# controlo_rev4.net
KiCad netlist of a schematic drawn in Altium Designer
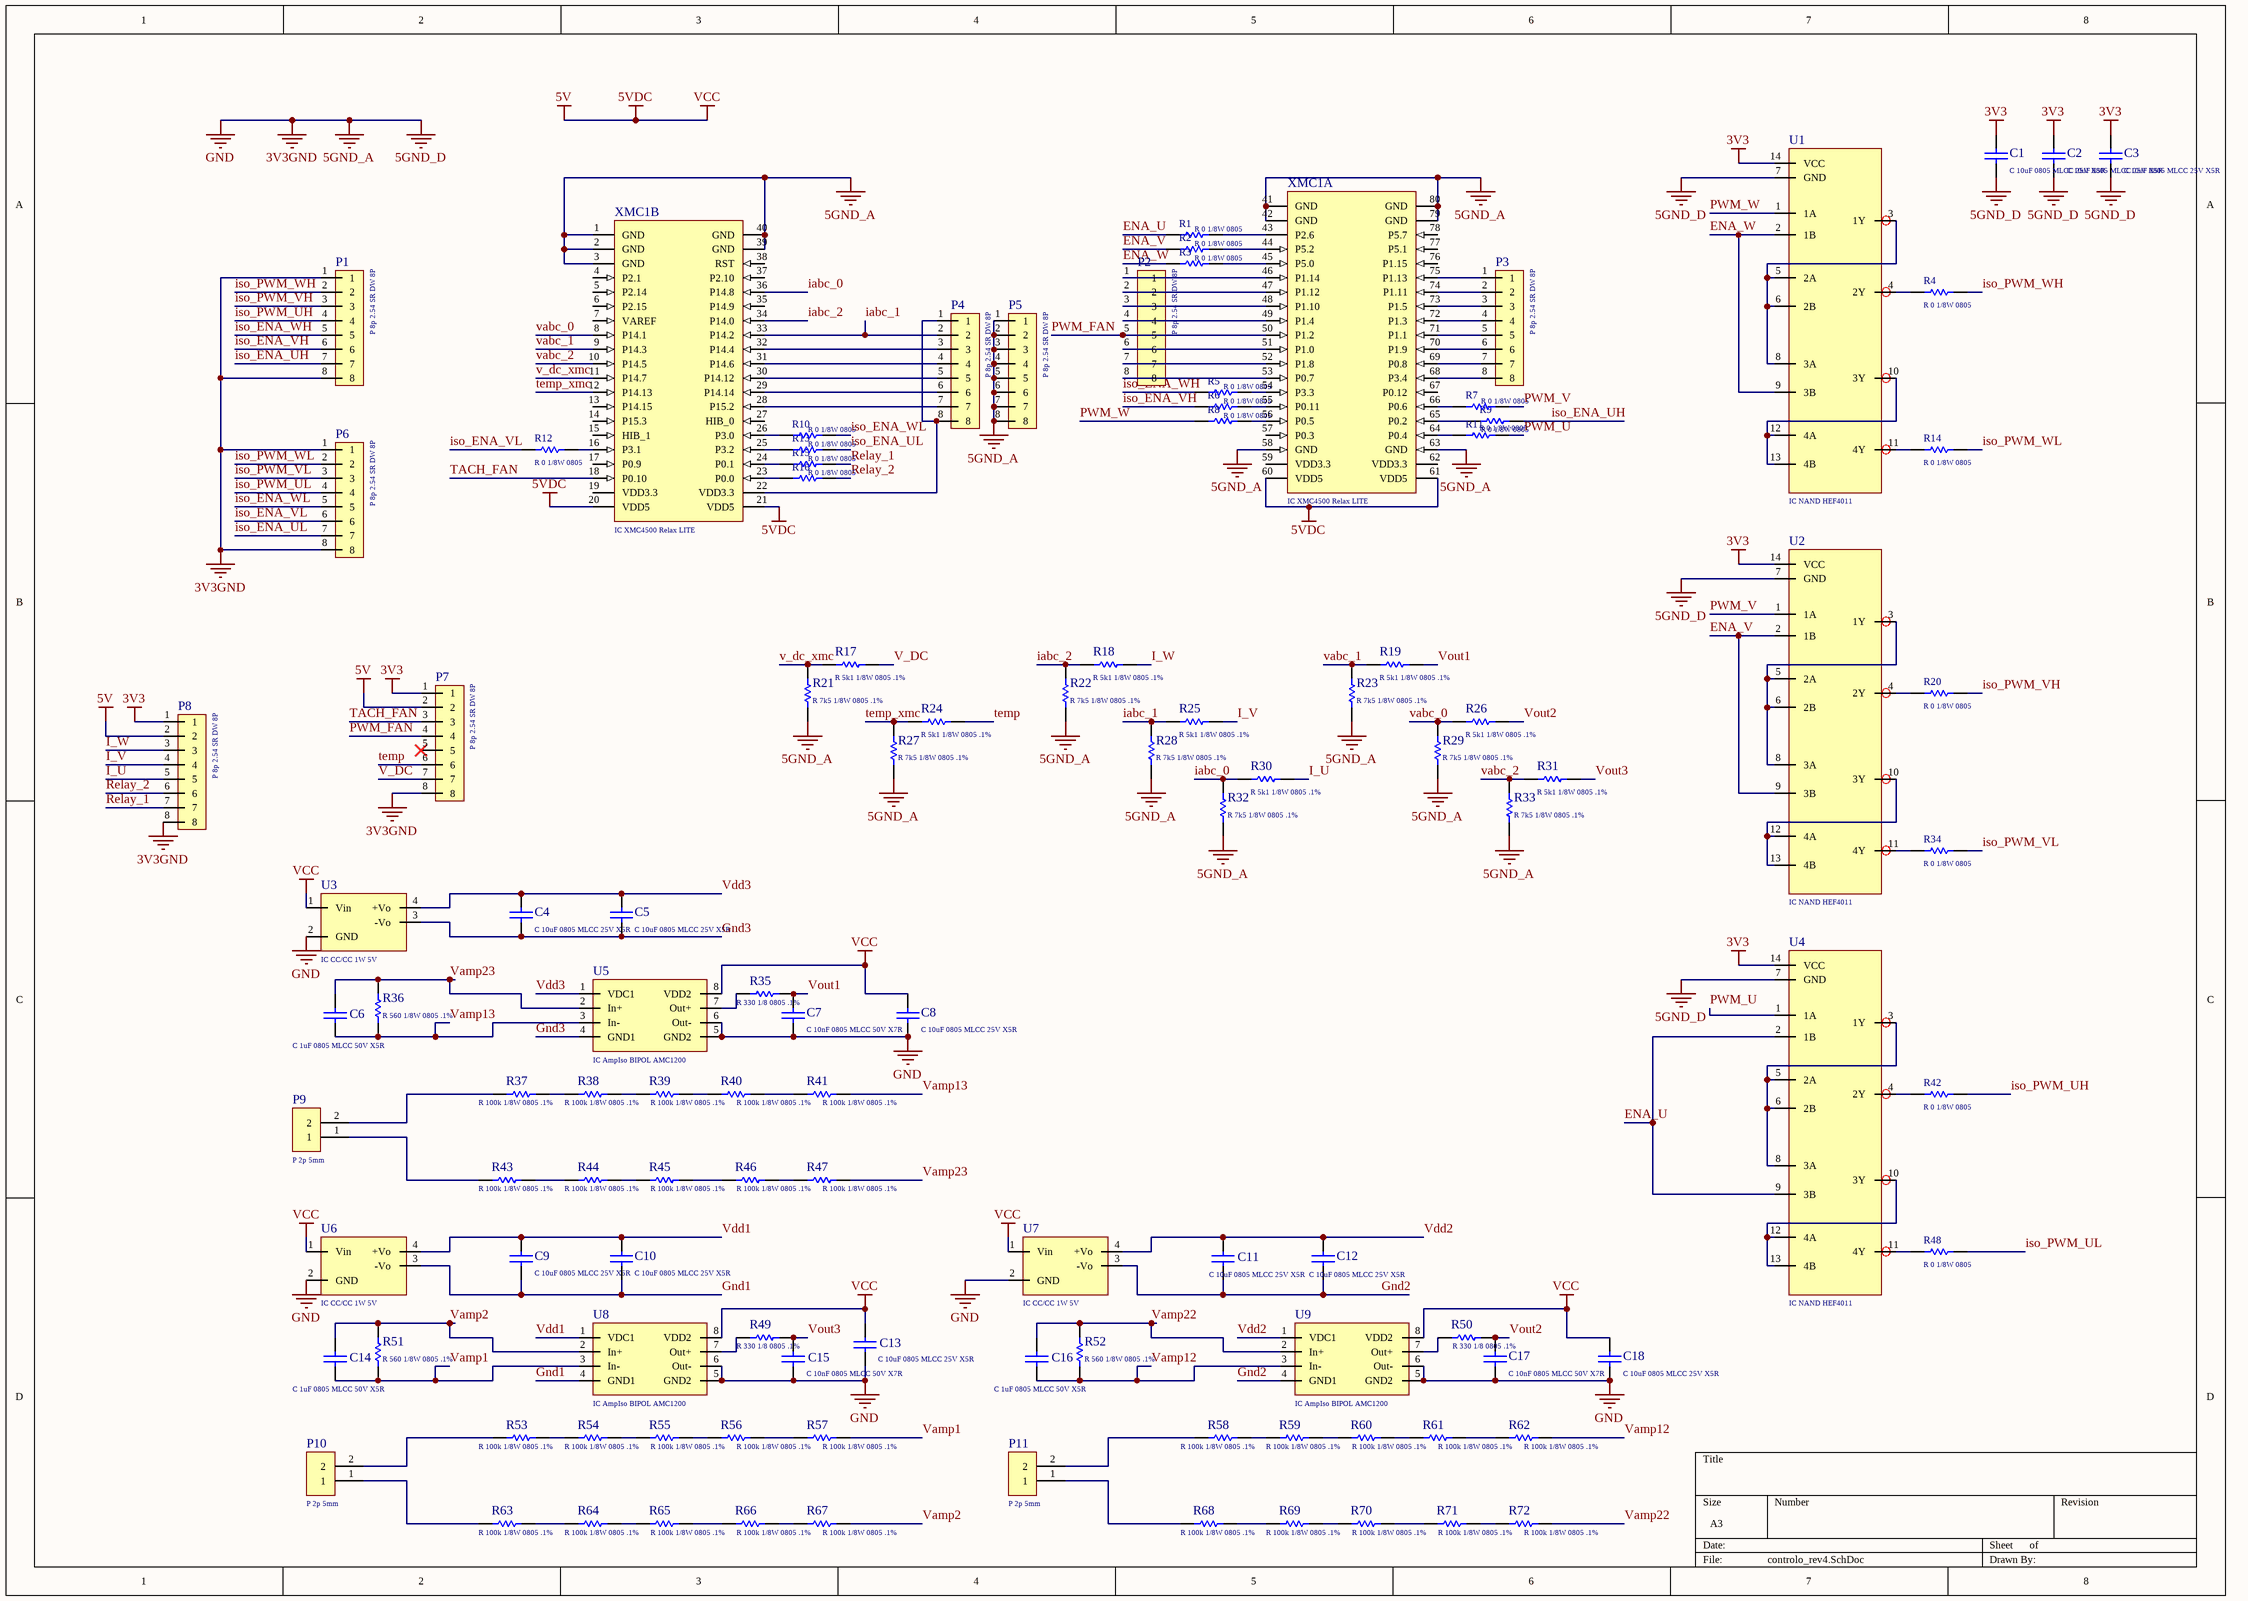
[diagram p0: controlo_rev4.SchDoc]

(export (version "E")
  (design (tool "Eeschema 10.0.6"))
  (components
    (comp (ref "C1")
      (value "C 10uF 0805 MLCC 25V X5R")
      (footprint "CAPC_0805")
      (description "Capacitores de cerâmica multicamada MLCC - SMD/SMT 10uF 25V X5R +/-10% 0805 Gen Purp")
      (fields (field (name "LCSC PART #") "C15850"))
      (libsource (lib "vi_measurement") (part "Capacitor SMD"))
    )
    (comp (ref "C2")
      (value "C 10uF 0805 MLCC 25V X5R")
      (footprint "CAPC_0805")
      (description "Capacitores de cerâmica multicamada MLCC - SMD/SMT 10uF 25V X5R +/-10% 0805 Gen Purp")
      (fields (field (name "LCSC PART #") "C15850"))
      (libsource (lib "vi_measurement") (part "Capacitor SMD"))
    )
    (comp (ref "C3")
      (value "C 10uF 0805 MLCC 25V X5R")
      (footprint "CAPC_0805")
      (description "Capacitores de cerâmica multicamada MLCC - SMD/SMT 10uF 25V X5R +/-10% 0805 Gen Purp")
      (fields (field (name "LCSC PART #") "C15850"))
      (libsource (lib "vi_measurement") (part "Capacitor SMD"))
    )
    (comp (ref "C4")
      (value "C 10uF 0805 MLCC 25V X5R")
      (footprint "CAPC_0805")
      (description "Capacitores de cerâmica multicamada MLCC - SMD/SMT 10uF 25V X5R +/-10% 0805 Gen Purp")
      (fields (field (name "LCSC PART #") "C15850"))
      (libsource (lib "vi_measurement") (part "Capacitor SMD"))
    )
    (comp (ref "C5")
      (value "C 10uF 0805 MLCC 25V X5R")
      (footprint "CAPC_0805")
      (description "Capacitores de cerâmica multicamada MLCC - SMD/SMT 10uF 25V X5R +/-10% 0805 Gen Purp")
      (fields (field (name "LCSC PART #") "C15850"))
      (libsource (lib "vi_measurement") (part "Capacitor SMD"))
    )
    (comp (ref "C6")
      (value "C 1uF 0805 MLCC 50V X5R")
      (footprint "CAPC_0805")
      (description "Capacitores de cerâmica multicamada MLCC - SMD/SMT 0805 50V 1uF 20% X5R")
      (fields (field (name "LCSC PART #") "C28323"))
      (libsource (lib "vi_measurement") (part "Capacitor SMD"))
    )
    (comp (ref "C7")
      (value "C 10nF 0805 MLCC 50V X7R")
      (footprint "CAPC_0805")
      (description "Capacitores de cerâmica multicamada MLCC - SMD/SMT 10nF 50V X7R 10%")
      (fields (field (name "LCSC PART #") "C1710"))
      (libsource (lib "vi_measurement") (part "Capacitor SMD"))
    )
    (comp (ref "C8")
      (value "C 10uF 0805 MLCC 25V X5R")
      (footprint "CAPC_0805")
      (description "Capacitores de cerâmica multicamada MLCC - SMD/SMT 10uF 25V X5R +/-10% 0805 Gen Purp")
      (fields (field (name "LCSC PART #") "C15850"))
      (libsource (lib "vi_measurement") (part "Capacitor SMD"))
    )
    (comp (ref "C9")
      (value "C 10uF 0805 MLCC 25V X5R")
      (footprint "CAPC_0805")
      (description "Capacitores de cerâmica multicamada MLCC - SMD/SMT 10uF 25V X5R +/-10% 0805 Gen Purp")
      (fields (field (name "LCSC PART #") "C15850"))
      (libsource (lib "vi_measurement") (part "Capacitor SMD"))
    )
    (comp (ref "C10")
      (value "C 10uF 0805 MLCC 25V X5R")
      (footprint "CAPC_0805")
      (description "Capacitores de cerâmica multicamada MLCC - SMD/SMT 10uF 25V X5R +/-10% 0805 Gen Purp")
      (fields (field (name "LCSC PART #") "C15850"))
      (libsource (lib "vi_measurement") (part "Capacitor SMD"))
    )
    (comp (ref "C11")
      (value "C 10uF 0805 MLCC 25V X5R")
      (footprint "CAPC_0805")
      (description "Capacitores de cerâmica multicamada MLCC - SMD/SMT 10uF 25V X5R +/-10% 0805 Gen Purp")
      (fields (field (name "LCSC PART #") "C15850"))
      (libsource (lib "vi_measurement") (part "Capacitor SMD"))
    )
    (comp (ref "C12")
      (value "C 10uF 0805 MLCC 25V X5R")
      (footprint "CAPC_0805")
      (description "Capacitores de cerâmica multicamada MLCC - SMD/SMT 10uF 25V X5R +/-10% 0805 Gen Purp")
      (fields (field (name "LCSC PART #") "C15850"))
      (libsource (lib "vi_measurement") (part "Capacitor SMD"))
    )
    (comp (ref "C13")
      (value "C 10uF 0805 MLCC 25V X5R")
      (footprint "CAPC_0805")
      (description "Capacitores de cerâmica multicamada MLCC - SMD/SMT 10uF 25V X5R +/-10% 0805 Gen Purp")
      (fields (field (name "LCSC PART #") "C15850"))
      (libsource (lib "vi_measurement") (part "Capacitor SMD"))
    )
    (comp (ref "C14")
      (value "C 1uF 0805 MLCC 50V X5R")
      (footprint "CAPC_0805")
      (description "Capacitores de cerâmica multicamada MLCC - SMD/SMT 0805 50V 1uF 20% X5R")
      (fields (field (name "LCSC PART #") "C28323"))
      (libsource (lib "vi_measurement") (part "Capacitor SMD"))
    )
    (comp (ref "C15")
      (value "C 10nF 0805 MLCC 50V X7R")
      (footprint "CAPC_0805")
      (description "Capacitores de cerâmica multicamada MLCC - SMD/SMT 10nF 50V X7R 10%")
      (fields (field (name "LCSC PART #") "C1710"))
      (libsource (lib "vi_measurement") (part "Capacitor SMD"))
    )
    (comp (ref "C16")
      (value "C 1uF 0805 MLCC 50V X5R")
      (footprint "CAPC_0805")
      (description "Capacitores de cerâmica multicamada MLCC - SMD/SMT 0805 50V 1uF 20% X5R")
      (fields (field (name "LCSC PART #") "C28323"))
      (libsource (lib "vi_measurement") (part "Capacitor SMD"))
    )
    (comp (ref "C17")
      (value "C 10nF 0805 MLCC 50V X7R")
      (footprint "CAPC_0805")
      (description "Capacitores de cerâmica multicamada MLCC - SMD/SMT 10nF 50V X7R 10%")
      (fields (field (name "LCSC PART #") "C1710"))
      (libsource (lib "vi_measurement") (part "Capacitor SMD"))
    )
    (comp (ref "C18")
      (value "C 10uF 0805 MLCC 25V X5R")
      (footprint "CAPC_0805")
      (description "Capacitores de cerâmica multicamada MLCC - SMD/SMT 10uF 25V X5R +/-10% 0805 Gen Purp")
      (fields (field (name "LCSC PART #") "C15850"))
      (libsource (lib "vi_measurement") (part "Capacitor SMD"))
    )
    (comp (ref "P1")
      (value "P 8p 2.54 SR DW 8P")
      (footprint "Header 8x1 8.5mm")
      (description "Distribuidores e Alojamento de Fios CGrid Hrd SRDW THo le 8ckt")
      (libsource (lib "vmorais_libraries") (part "jumper_8p"))
    )
    (comp (ref "P2")
      (value "P 8p 2.54 SR DW 8P")
      (footprint "Header 8x1 8.5mm")
      (description "Distribuidores e Alojamento de Fios CGrid Hrd SRDW THo le 8ckt")
      (libsource (lib "vmorais_libraries") (part "jumper_8p"))
    )
    (comp (ref "P3")
      (value "P 8p 2.54 SR DW 8P")
      (footprint "Header 8x1 8.5mm")
      (description "Distribuidores e Alojamento de Fios CGrid Hrd SRDW THo le 8ckt")
      (libsource (lib "vmorais_libraries") (part "jumper_8p"))
    )
    (comp (ref "P4")
      (value "P 8p 2.54 SR DW 8P")
      (footprint "Header 8x1 8.5mm")
      (description "Distribuidores e Alojamento de Fios CGrid Hrd SRDW THo le 8ckt")
      (libsource (lib "vmorais_libraries") (part "jumper_8p"))
    )
    (comp (ref "P5")
      (value "P 8p 2.54 SR DW 8P")
      (footprint "Header 8x1 8.5mm")
      (description "Distribuidores e Alojamento de Fios CGrid Hrd SRDW THo le 8ckt")
      (libsource (lib "vmorais_libraries") (part "jumper_8p"))
    )
    (comp (ref "P6")
      (value "P 8p 2.54 SR DW 8P")
      (footprint "Header 8x1 8.5mm")
      (description "Distribuidores e Alojamento de Fios CGrid Hrd SRDW THo le 8ckt")
      (libsource (lib "vmorais_libraries") (part "jumper_8p"))
    )
    (comp (ref "P7")
      (value "P 8p 2.54 SR DW 8P")
      (footprint "Header 8x1 8.5mm")
      (description "Distribuidores e Alojamento de Fios CGrid Hrd SRDW THo le 8ckt")
      (libsource (lib "vmorais_libraries") (part "jumper_8p"))
    )
    (comp (ref "P8")
      (value "P 8p 2.54 SR DW 8P")
      (footprint "Header 8x1 8.5mm")
      (description "Distribuidores e Alojamento de Fios CGrid Hrd SRDW THo le 8ckt")
      (libsource (lib "vmorais_libraries") (part "jumper_8p"))
    )
    (comp (ref "P9")
      (value "P 2p 5mm")
      (footprint "connector1x2_parafuso")
      (description "Bloques de terminales de PCB de perfil estándar RS de 5,0 mm")
      (libsource (lib "malvega_pcb") (part "gen_purpose_conn_1x2"))
    )
    (comp (ref "P10")
      (value "P 2p 5mm")
      (footprint "connector1x2_parafuso")
      (description "Bloques de terminales de PCB de perfil estándar RS de 5,0 mm")
      (libsource (lib "malvega_pcb") (part "gen_purpose_conn_1x2"))
    )
    (comp (ref "P11")
      (value "P 2p 5mm")
      (footprint "connector1x2_parafuso")
      (description "Bloques de terminales de PCB de perfil estándar RS de 5,0 mm")
      (libsource (lib "malvega_pcb") (part "gen_purpose_conn_1x2"))
    )
    (comp (ref "R1")
      (value "R 0 1/8W 0805")
      (footprint "RESC_0805")
      (description "Resistores de Filme Espesso - SMD 1/8Watt 0ohms Commercial Use")
      (fields (field (name "LCSC PART #") "C17477"))
      (libsource (lib "inversor_50a") (part "Resistor"))
    )
    (comp (ref "R2")
      (value "R 0 1/8W 0805")
      (footprint "RESC_0805")
      (description "Resistores de Filme Espesso - SMD 1/8Watt 0ohms Commercial Use")
      (fields (field (name "LCSC PART #") "C17477"))
      (libsource (lib "inversor_50a") (part "Resistor"))
    )
    (comp (ref "R3")
      (value "R 0 1/8W 0805")
      (footprint "RESC_0805")
      (description "Resistores de Filme Espesso - SMD 1/8Watt 0ohms Commercial Use")
      (fields (field (name "LCSC PART #") "C17477"))
      (libsource (lib "inversor_50a") (part "Resistor"))
    )
    (comp (ref "R4")
      (value "R 0 1/8W 0805")
      (footprint "RESC_0805")
      (description "Resistores de Filme Espesso - SMD 1/8Watt 0ohms Commercial Use")
      (fields (field (name "LCSC PART #") "C17477"))
      (libsource (lib "inversor_50a") (part "Resistor"))
    )
    (comp (ref "R5")
      (value "R 0 1/8W 0805")
      (footprint "RESC_0805")
      (description "Resistores de Filme Espesso - SMD 1/8Watt 0ohms Commercial Use")
      (fields (field (name "LCSC PART #") "C17477"))
      (libsource (lib "inversor_50a") (part "Resistor"))
    )
    (comp (ref "R6")
      (value "R 0 1/8W 0805")
      (footprint "RESC_0805")
      (description "Resistores de Filme Espesso - SMD 1/8Watt 0ohms Commercial Use")
      (fields (field (name "LCSC PART #") "C17477"))
      (libsource (lib "inversor_50a") (part "Resistor"))
    )
    (comp (ref "R7")
      (value "R 0 1/8W 0805")
      (footprint "RESC_0805")
      (description "Resistores de Filme Espesso - SMD 1/8Watt 0ohms Commercial Use")
      (fields (field (name "LCSC PART #") "C17477"))
      (libsource (lib "inversor_50a") (part "Resistor"))
    )
    (comp (ref "R8")
      (value "R 0 1/8W 0805")
      (footprint "RESC_0805")
      (description "Resistores de Filme Espesso - SMD 1/8Watt 0ohms Commercial Use")
      (fields (field (name "LCSC PART #") "C17477"))
      (libsource (lib "inversor_50a") (part "Resistor"))
    )
    (comp (ref "R9")
      (value "R 0 1/8W 0805")
      (footprint "RESC_0805")
      (description "Resistores de Filme Espesso - SMD 1/8Watt 0ohms Commercial Use")
      (fields (field (name "LCSC PART #") "C17477"))
      (libsource (lib "inversor_50a") (part "Resistor"))
    )
    (comp (ref "R10")
      (value "R 0 1/8W 0805")
      (footprint "RESC_0805")
      (description "Resistores de Filme Espesso - SMD 1/8Watt 0ohms Commercial Use")
      (fields (field (name "LCSC PART #") "C17477"))
      (libsource (lib "inversor_50a") (part "Resistor"))
    )
    (comp (ref "R11")
      (value "R 0 1/8W 0805")
      (footprint "RESC_0805")
      (description "Resistores de Filme Espesso - SMD 1/8Watt 0ohms Commercial Use")
      (fields (field (name "LCSC PART #") "C17477"))
      (libsource (lib "inversor_50a") (part "Resistor"))
    )
    (comp (ref "R12")
      (value "R 0 1/8W 0805")
      (footprint "RESC_0805")
      (description "Resistores de Filme Espesso - SMD 1/8Watt 0ohms Commercial Use")
      (fields (field (name "LCSC PART #") "C17477"))
      (libsource (lib "inversor_50a") (part "Resistor"))
    )
    (comp (ref "R13")
      (value "R 0 1/8W 0805")
      (footprint "RESC_0805")
      (description "Resistores de Filme Espesso - SMD 1/8Watt 0ohms Commercial Use")
      (fields (field (name "LCSC PART #") "C17477"))
      (libsource (lib "inversor_50a") (part "Resistor"))
    )
    (comp (ref "R14")
      (value "R 0 1/8W 0805")
      (footprint "RESC_0805")
      (description "Resistores de Filme Espesso - SMD 1/8Watt 0ohms Commercial Use")
      (fields (field (name "LCSC PART #") "C17477"))
      (libsource (lib "inversor_50a") (part "Resistor"))
    )
    (comp (ref "R15")
      (value "R 0 1/8W 0805")
      (footprint "RESC_0805")
      (description "Resistores de Filme Espesso - SMD 1/8Watt 0ohms Commercial Use")
      (fields (field (name "LCSC PART #") "C17477"))
      (libsource (lib "inversor_50a") (part "Resistor"))
    )
    (comp (ref "R16")
      (value "R 0 1/8W 0805")
      (footprint "RESC_0805")
      (description "Resistores de Filme Espesso - SMD 1/8Watt 0ohms Commercial Use")
      (fields (field (name "LCSC PART #") "C17477"))
      (libsource (lib "inversor_50a") (part "Resistor"))
    )
    (comp (ref "R17")
      (value "R 5k1 1/8W 0805 .1%")
      (footprint "RESC_0805")
      (description "Resistores de Filme Fino - SMD 0805 5.1Kohm 1/8W .1% 25ppm")
      (fields (field (name "LCSC PART #") "C27834"))
      (libsource (lib "inversor_50a") (part "Resistor"))
    )
    (comp (ref "R18")
      (value "R 5k1 1/8W 0805 .1%")
      (footprint "RESC_0805")
      (description "Resistores de Filme Fino - SMD 0805 5.1Kohm 1/8W .1% 25ppm")
      (fields (field (name "LCSC PART #") "C27834"))
      (libsource (lib "inversor_50a") (part "Resistor"))
    )
    (comp (ref "R19")
      (value "R 5k1 1/8W 0805 .1%")
      (footprint "RESC_0805")
      (description "Resistores de Filme Fino - SMD 0805 5.1Kohm 1/8W .1% 25ppm")
      (fields (field (name "LCSC PART #") "C27834"))
      (libsource (lib "inversor_50a") (part "Resistor"))
    )
    (comp (ref "R20")
      (value "R 0 1/8W 0805")
      (footprint "RESC_0805")
      (description "Resistores de Filme Espesso - SMD 1/8Watt 0ohms Commercial Use")
      (fields (field (name "LCSC PART #") "C17477"))
      (libsource (lib "inversor_50a") (part "Resistor"))
    )
    (comp (ref "R21")
      (value "R 7k5 1/8W 0805 .1%")
      (footprint "RESC_0805")
      (description "Resistores de Filme Fino - SMD 7.5K OHM .1% 25ppm")
      (fields (field (name "LCSC PART #") "C17807"))
      (libsource (lib "inversor_50a") (part "Resistor"))
    )
    (comp (ref "R22")
      (value "R 7k5 1/8W 0805 .1%")
      (footprint "RESC_0805")
      (description "Resistores de Filme Fino - SMD 7.5K OHM .1% 25ppm")
      (fields (field (name "LCSC PART #") "C17807"))
      (libsource (lib "inversor_50a") (part "Resistor"))
    )
    (comp (ref "R23")
      (value "R 7k5 1/8W 0805 .1%")
      (footprint "RESC_0805")
      (description "Resistores de Filme Fino - SMD 7.5K OHM .1% 25ppm")
      (fields (field (name "LCSC PART #") "C17807"))
      (libsource (lib "inversor_50a") (part "Resistor"))
    )
    (comp (ref "R24")
      (value "R 5k1 1/8W 0805 .1%")
      (footprint "RESC_0805")
      (description "Resistores de Filme Fino - SMD 0805 5.1Kohm 1/8W .1% 25ppm")
      (fields (field (name "LCSC PART #") "C27834"))
      (libsource (lib "inversor_50a") (part "Resistor"))
    )
    (comp (ref "R25")
      (value "R 5k1 1/8W 0805 .1%")
      (footprint "RESC_0805")
      (description "Resistores de Filme Fino - SMD 0805 5.1Kohm 1/8W .1% 25ppm")
      (fields (field (name "LCSC PART #") "C27834"))
      (libsource (lib "inversor_50a") (part "Resistor"))
    )
    (comp (ref "R26")
      (value "R 5k1 1/8W 0805 .1%")
      (footprint "RESC_0805")
      (description "Resistores de Filme Fino - SMD 0805 5.1Kohm 1/8W .1% 25ppm")
      (fields (field (name "LCSC PART #") "C27834"))
      (libsource (lib "inversor_50a") (part "Resistor"))
    )
    (comp (ref "R27")
      (value "R 7k5 1/8W 0805 .1%")
      (footprint "RESC_0805")
      (description "Resistores de Filme Fino - SMD 7.5K OHM .1% 25ppm")
      (fields (field (name "LCSC PART #") "C17807"))
      (libsource (lib "inversor_50a") (part "Resistor"))
    )
    (comp (ref "R28")
      (value "R 7k5 1/8W 0805 .1%")
      (footprint "RESC_0805")
      (description "Resistores de Filme Fino - SMD 7.5K OHM .1% 25ppm")
      (fields (field (name "LCSC PART #") "C17807"))
      (libsource (lib "inversor_50a") (part "Resistor"))
    )
    (comp (ref "R29")
      (value "R 7k5 1/8W 0805 .1%")
      (footprint "RESC_0805")
      (description "Resistores de Filme Fino - SMD 7.5K OHM .1% 25ppm")
      (fields (field (name "LCSC PART #") "C17807"))
      (libsource (lib "inversor_50a") (part "Resistor"))
    )
    (comp (ref "R30")
      (value "R 5k1 1/8W 0805 .1%")
      (footprint "RESC_0805")
      (description "Resistores de Filme Fino - SMD 0805 5.1Kohm 1/8W .1% 25ppm")
      (fields (field (name "LCSC PART #") "C27834"))
      (libsource (lib "inversor_50a") (part "Resistor"))
    )
    (comp (ref "R31")
      (value "R 5k1 1/8W 0805 .1%")
      (footprint "RESC_0805")
      (description "Resistores de Filme Fino - SMD 0805 5.1Kohm 1/8W .1% 25ppm")
      (fields (field (name "LCSC PART #") "C27834"))
      (libsource (lib "inversor_50a") (part "Resistor"))
    )
    (comp (ref "R32")
      (value "R 7k5 1/8W 0805 .1%")
      (footprint "RESC_0805")
      (description "Resistores de Filme Fino - SMD 7.5K OHM .1% 25ppm")
      (fields (field (name "LCSC PART #") "C17807"))
      (libsource (lib "inversor_50a") (part "Resistor"))
    )
    (comp (ref "R33")
      (value "R 7k5 1/8W 0805 .1%")
      (footprint "RESC_0805")
      (description "Resistores de Filme Fino - SMD 7.5K OHM .1% 25ppm")
      (fields (field (name "LCSC PART #") "C17807"))
      (libsource (lib "inversor_50a") (part "Resistor"))
    )
    (comp (ref "R34")
      (value "R 0 1/8W 0805")
      (footprint "RESC_0805")
      (description "Resistores de Filme Espesso - SMD 1/8Watt 0ohms Commercial Use")
      (fields (field (name "LCSC PART #") "C17477"))
      (libsource (lib "inversor_50a") (part "Resistor"))
    )
    (comp (ref "R35")
      (value "R 330 1/8 0805 .1%")
      (footprint "RESC_0805")
      (description "Resistores de Filme Fino - SMD CPF 0805 330R 0.1% 25PPM 1K RL")
      (fields (field (name "LCSC PART #") "C17630"))
      (libsource (lib "inversor_50a") (part "Resistor"))
    )
    (comp (ref "R36")
      (value "R 560 1/8W 0805 .1%")
      (footprint "RESC_0805")
      (description "Resistores de Filme Fino - SMD 1/8W 3.6K ohm .1% 25ppm")
      (fields (field (name "LCSC PART #") "C28636"))
      (libsource (lib "inversor_50a") (part "Resistor"))
    )
    (comp (ref "R37")
      (value "R 100k 1/8W 0805 .1%")
      (footprint "RESC_0805")
      (description "Resistores de Filme Fino - SMD 100 Kohm .1% 0805 25PPM")
      (fields (field (name "LCSC PART #") "C17407"))
      (libsource (lib "inversor_50a") (part "Resistor"))
    )
    (comp (ref "R38")
      (value "R 100k 1/8W 0805 .1%")
      (footprint "RESC_0805")
      (description "Resistores de Filme Fino - SMD 100 Kohm .1% 0805 25PPM")
      (fields (field (name "LCSC PART #") "C17407"))
      (libsource (lib "inversor_50a") (part "Resistor"))
    )
    (comp (ref "R39")
      (value "R 100k 1/8W 0805 .1%")
      (footprint "RESC_0805")
      (description "Resistores de Filme Fino - SMD 100 Kohm .1% 0805 25PPM")
      (fields (field (name "LCSC PART #") "C17407"))
      (libsource (lib "inversor_50a") (part "Resistor"))
    )
    (comp (ref "R40")
      (value "R 100k 1/8W 0805 .1%")
      (footprint "RESC_0805")
      (description "Resistores de Filme Fino - SMD 100 Kohm .1% 0805 25PPM")
      (fields (field (name "LCSC PART #") "C17407"))
      (libsource (lib "inversor_50a") (part "Resistor"))
    )
    (comp (ref "R41")
      (value "R 100k 1/8W 0805 .1%")
      (footprint "RESC_0805")
      (description "Resistores de Filme Fino - SMD 100 Kohm .1% 0805 25PPM")
      (fields (field (name "LCSC PART #") "C17407"))
      (libsource (lib "inversor_50a") (part "Resistor"))
    )
    (comp (ref "R42")
      (value "R 0 1/8W 0805")
      (footprint "RESC_0805")
      (description "Resistores de Filme Espesso - SMD 1/8Watt 0ohms Commercial Use")
      (fields (field (name "LCSC PART #") "C17477"))
      (libsource (lib "inversor_50a") (part "Resistor"))
    )
    (comp (ref "R43")
      (value "R 100k 1/8W 0805 .1%")
      (footprint "RESC_0805")
      (description "Resistores de Filme Fino - SMD 100 Kohm .1% 0805 25PPM")
      (fields (field (name "LCSC PART #") "C17407"))
      (libsource (lib "inversor_50a") (part "Resistor"))
    )
    (comp (ref "R44")
      (value "R 100k 1/8W 0805 .1%")
      (footprint "RESC_0805")
      (description "Resistores de Filme Fino - SMD 100 Kohm .1% 0805 25PPM")
      (fields (field (name "LCSC PART #") "C17407"))
      (libsource (lib "inversor_50a") (part "Resistor"))
    )
    (comp (ref "R45")
      (value "R 100k 1/8W 0805 .1%")
      (footprint "RESC_0805")
      (description "Resistores de Filme Fino - SMD 100 Kohm .1% 0805 25PPM")
      (fields (field (name "LCSC PART #") "C17407"))
      (libsource (lib "inversor_50a") (part "Resistor"))
    )
    (comp (ref "R46")
      (value "R 100k 1/8W 0805 .1%")
      (footprint "RESC_0805")
      (description "Resistores de Filme Fino - SMD 100 Kohm .1% 0805 25PPM")
      (fields (field (name "LCSC PART #") "C17407"))
      (libsource (lib "inversor_50a") (part "Resistor"))
    )
    (comp (ref "R47")
      (value "R 100k 1/8W 0805 .1%")
      (footprint "RESC_0805")
      (description "Resistores de Filme Fino - SMD 100 Kohm .1% 0805 25PPM")
      (fields (field (name "LCSC PART #") "C17407"))
      (libsource (lib "inversor_50a") (part "Resistor"))
    )
    (comp (ref "R48")
      (value "R 0 1/8W 0805")
      (footprint "RESC_0805")
      (description "Resistores de Filme Espesso - SMD 1/8Watt 0ohms Commercial Use")
      (fields (field (name "LCSC PART #") "C17477"))
      (libsource (lib "inversor_50a") (part "Resistor"))
    )
    (comp (ref "R49")
      (value "R 330 1/8 0805 .1%")
      (footprint "RESC_0805")
      (description "Resistores de Filme Fino - SMD CPF 0805 330R 0.1% 25PPM 1K RL")
      (fields (field (name "LCSC PART #") "C17630"))
      (libsource (lib "inversor_50a") (part "Resistor"))
    )
    (comp (ref "R50")
      (value "R 330 1/8 0805 .1%")
      (footprint "RESC_0805")
      (description "Resistores de Filme Fino - SMD CPF 0805 330R 0.1% 25PPM 1K RL")
      (fields (field (name "LCSC PART #") "C17630"))
      (libsource (lib "inversor_50a") (part "Resistor"))
    )
    (comp (ref "R51")
      (value "R 560 1/8W 0805 .1%")
      (footprint "RESC_0805")
      (description "Resistores de Filme Fino - SMD 1/8W 3.6K ohm .1% 25ppm")
      (fields (field (name "LCSC PART #") "C28636"))
      (libsource (lib "inversor_50a") (part "Resistor"))
    )
    (comp (ref "R52")
      (value "R 560 1/8W 0805 .1%")
      (footprint "RESC_0805")
      (description "Resistores de Filme Fino - SMD 1/8W 3.6K ohm .1% 25ppm")
      (fields (field (name "LCSC PART #") "C28636"))
      (libsource (lib "inversor_50a") (part "Resistor"))
    )
    (comp (ref "R53")
      (value "R 100k 1/8W 0805 .1%")
      (footprint "RESC_0805")
      (description "Resistores de Filme Fino - SMD 100 Kohm .1% 0805 25PPM")
      (fields (field (name "LCSC PART #") "C17407"))
      (libsource (lib "inversor_50a") (part "Resistor"))
    )
    (comp (ref "R54")
      (value "R 100k 1/8W 0805 .1%")
      (footprint "RESC_0805")
      (description "Resistores de Filme Fino - SMD 100 Kohm .1% 0805 25PPM")
      (fields (field (name "LCSC PART #") "C17407"))
      (libsource (lib "inversor_50a") (part "Resistor"))
    )
    (comp (ref "R55")
      (value "R 100k 1/8W 0805 .1%")
      (footprint "RESC_0805")
      (description "Resistores de Filme Fino - SMD 100 Kohm .1% 0805 25PPM")
      (fields (field (name "LCSC PART #") "C17407"))
      (libsource (lib "inversor_50a") (part "Resistor"))
    )
    (comp (ref "R56")
      (value "R 100k 1/8W 0805 .1%")
      (footprint "RESC_0805")
      (description "Resistores de Filme Fino - SMD 100 Kohm .1% 0805 25PPM")
      (fields (field (name "LCSC PART #") "C17407"))
      (libsource (lib "inversor_50a") (part "Resistor"))
    )
    (comp (ref "R57")
      (value "R 100k 1/8W 0805 .1%")
      (footprint "RESC_0805")
      (description "Resistores de Filme Fino - SMD 100 Kohm .1% 0805 25PPM")
      (fields (field (name "LCSC PART #") "C17407"))
      (libsource (lib "inversor_50a") (part "Resistor"))
    )
    (comp (ref "R58")
      (value "R 100k 1/8W 0805 .1%")
      (footprint "RESC_0805")
      (description "Resistores de Filme Fino - SMD 100 Kohm .1% 0805 25PPM")
      (fields (field (name "LCSC PART #") "C17407"))
      (libsource (lib "inversor_50a") (part "Resistor"))
    )
    (comp (ref "R59")
      (value "R 100k 1/8W 0805 .1%")
      (footprint "RESC_0805")
      (description "Resistores de Filme Fino - SMD 100 Kohm .1% 0805 25PPM")
      (fields (field (name "LCSC PART #") "C17407"))
      (libsource (lib "inversor_50a") (part "Resistor"))
    )
    (comp (ref "R60")
      (value "R 100k 1/8W 0805 .1%")
      (footprint "RESC_0805")
      (description "Resistores de Filme Fino - SMD 100 Kohm .1% 0805 25PPM")
      (fields (field (name "LCSC PART #") "C17407"))
      (libsource (lib "inversor_50a") (part "Resistor"))
    )
    (comp (ref "R61")
      (value "R 100k 1/8W 0805 .1%")
      (footprint "RESC_0805")
      (description "Resistores de Filme Fino - SMD 100 Kohm .1% 0805 25PPM")
      (fields (field (name "LCSC PART #") "C17407"))
      (libsource (lib "inversor_50a") (part "Resistor"))
    )
    (comp (ref "R62")
      (value "R 100k 1/8W 0805 .1%")
      (footprint "RESC_0805")
      (description "Resistores de Filme Fino - SMD 100 Kohm .1% 0805 25PPM")
      (fields (field (name "LCSC PART #") "C17407"))
      (libsource (lib "inversor_50a") (part "Resistor"))
    )
    (comp (ref "R63")
      (value "R 100k 1/8W 0805 .1%")
      (footprint "RESC_0805")
      (description "Resistores de Filme Fino - SMD 100 Kohm .1% 0805 25PPM")
      (fields (field (name "LCSC PART #") "C17407"))
      (libsource (lib "inversor_50a") (part "Resistor"))
    )
    (comp (ref "R64")
      (value "R 100k 1/8W 0805 .1%")
      (footprint "RESC_0805")
      (description "Resistores de Filme Fino - SMD 100 Kohm .1% 0805 25PPM")
      (fields (field (name "LCSC PART #") "C17407"))
      (libsource (lib "inversor_50a") (part "Resistor"))
    )
    (comp (ref "R65")
      (value "R 100k 1/8W 0805 .1%")
      (footprint "RESC_0805")
      (description "Resistores de Filme Fino - SMD 100 Kohm .1% 0805 25PPM")
      (fields (field (name "LCSC PART #") "C17407"))
      (libsource (lib "inversor_50a") (part "Resistor"))
    )
    (comp (ref "R66")
      (value "R 100k 1/8W 0805 .1%")
      (footprint "RESC_0805")
      (description "Resistores de Filme Fino - SMD 100 Kohm .1% 0805 25PPM")
      (fields (field (name "LCSC PART #") "C17407"))
      (libsource (lib "inversor_50a") (part "Resistor"))
    )
    (comp (ref "R67")
      (value "R 100k 1/8W 0805 .1%")
      (footprint "RESC_0805")
      (description "Resistores de Filme Fino - SMD 100 Kohm .1% 0805 25PPM")
      (fields (field (name "LCSC PART #") "C17407"))
      (libsource (lib "inversor_50a") (part "Resistor"))
    )
    (comp (ref "R68")
      (value "R 100k 1/8W 0805 .1%")
      (footprint "RESC_0805")
      (description "Resistores de Filme Fino - SMD 100 Kohm .1% 0805 25PPM")
      (fields (field (name "LCSC PART #") "C17407"))
      (libsource (lib "inversor_50a") (part "Resistor"))
    )
    (comp (ref "R69")
      (value "R 100k 1/8W 0805 .1%")
      (footprint "RESC_0805")
      (description "Resistores de Filme Fino - SMD 100 Kohm .1% 0805 25PPM")
      (fields (field (name "LCSC PART #") "C17407"))
      (libsource (lib "inversor_50a") (part "Resistor"))
    )
    (comp (ref "R70")
      (value "R 100k 1/8W 0805 .1%")
      (footprint "RESC_0805")
      (description "Resistores de Filme Fino - SMD 100 Kohm .1% 0805 25PPM")
      (fields (field (name "LCSC PART #") "C17407"))
      (libsource (lib "inversor_50a") (part "Resistor"))
    )
    (comp (ref "R71")
      (value "R 100k 1/8W 0805 .1%")
      (footprint "RESC_0805")
      (description "Resistores de Filme Fino - SMD 100 Kohm .1% 0805 25PPM")
      (fields (field (name "LCSC PART #") "C17407"))
      (libsource (lib "inversor_50a") (part "Resistor"))
    )
    (comp (ref "R72")
      (value "R 100k 1/8W 0805 .1%")
      (footprint "RESC_0805")
      (description "Resistores de Filme Fino - SMD 100 Kohm .1% 0805 25PPM")
      (fields (field (name "LCSC PART #") "C17407"))
      (libsource (lib "inversor_50a") (part "Resistor"))
    )
    (comp (ref "U1")
      (value "IC NAND HEF4011")
      (footprint "SOIC-14N")
      (description "Portas lógicas QUADRUPLE 2-INPUT NAND GATE")
      (fields (field (name "LCSC PART #") "C6725"))
      (libsource (lib "vmorais_libraries") (part "HEF4011"))
    )
    (comp (ref "U2")
      (value "IC NAND HEF4011")
      (footprint "SOIC-14N")
      (description "Portas lógicas QUADRUPLE 2-INPUT NAND GATE")
      (fields (field (name "LCSC PART #") "C6725"))
      (libsource (lib "vmorais_libraries") (part "HEF4011"))
    )
    (comp (ref "U3")
      (value "IC CC/CC 1W 5V")
      (footprint "DC/DC_ISO")
      (description "Conversores CC/CC com isolação 1W 5Vin 5Vout 200mA SIP7")
      (libsource (lib "vi_measurement") (part "DC/DC_ISO"))
    )
    (comp (ref "U4")
      (value "IC NAND HEF4011")
      (footprint "SOIC-14N")
      (description "Portas lógicas QUADRUPLE 2-INPUT NAND GATE")
      (fields (field (name "LCSC PART #") "C6725"))
      (libsource (lib "vmorais_libraries") (part "HEF4011"))
    )
    (comp (ref "U5")
      (value "IC AmpIso BIPOL AMC1200")
      (footprint "SOIC8")
      (description "Amplificadores de isolamento 4kV peak Iso Amp")
      (fields (field (name "LCSC PART #") "C79905"))
      (libsource (lib "vi_measurement") (part "AMC1200"))
    )
    (comp (ref "U6")
      (value "IC CC/CC 1W 5V")
      (footprint "DC/DC_ISO")
      (description "Conversores CC/CC com isolação 1W 5Vin 5Vout 200mA SIP7")
      (libsource (lib "vi_measurement") (part "DC/DC_ISO"))
    )
    (comp (ref "U7")
      (value "IC CC/CC 1W 5V")
      (footprint "DC/DC_ISO")
      (description "Conversores CC/CC com isolação 1W 5Vin 5Vout 200mA SIP7")
      (libsource (lib "vi_measurement") (part "DC/DC_ISO"))
    )
    (comp (ref "U8")
      (value "IC AmpIso BIPOL AMC1200")
      (footprint "SOIC8")
      (description "Amplificadores de isolamento 4kV peak Iso Amp")
      (fields (field (name "LCSC PART #") "C79905"))
      (libsource (lib "vi_measurement") (part "AMC1200"))
    )
    (comp (ref "U9")
      (value "IC AmpIso BIPOL AMC1200")
      (footprint "SOIC8")
      (description "Amplificadores de isolamento 4kV peak Iso Amp")
      (fields (field (name "LCSC PART #") "C79905"))
      (libsource (lib "vi_measurement") (part "AMC1200"))
    )
    (comp (ref "XMC1")
      (value "IC XMC4500 Relax LITE")
      (footprint "XMC4500")
      (libsource (lib "vmorais_libraries") (part "XMC4500"))
    )
  )
  (nets
    (net (code "1") (name "/ENA_U") (class "Default")
      (node (ref "R1") (pin "1") (pinfunction "1_1") (pintype "passive"))
      (node (ref "U4") (pin "2") (pinfunction "1B_2") (pintype "passive"))
      (node (ref "U4") (pin "9") (pinfunction "3B_9") (pintype "passive"))
    )
    (net (code "2") (name "/ENA_V") (class "Default")
      (node (ref "R2") (pin "1") (pinfunction "1_1") (pintype "passive"))
      (node (ref "U2") (pin "2") (pinfunction "1B_2") (pintype "passive"))
      (node (ref "U2") (pin "9") (pinfunction "3B_9") (pintype "passive"))
    )
    (net (code "3") (name "/ENA_W") (class "Default")
      (node (ref "R3") (pin "1") (pinfunction "1_1") (pintype "passive"))
      (node (ref "U1") (pin "2") (pinfunction "1B_2") (pintype "passive"))
      (node (ref "U1") (pin "9") (pinfunction "3B_9") (pintype "passive"))
    )
    (net (code "4") (name "/Gnd1") (class "Default")
      (node (ref "C10") (pin "1") (pinfunction "1_1") (pintype "passive"))
      (node (ref "C9") (pin "1") (pinfunction "1_1") (pintype "passive"))
      (node (ref "U6") (pin "3") (pinfunction "-Vo_3") (pintype "passive"))
      (node (ref "U8") (pin "4") (pinfunction "GND1_4") (pintype "passive"))
    )
    (net (code "5") (name "/Gnd2") (class "Default")
      (node (ref "C11") (pin "1") (pinfunction "1_1") (pintype "passive"))
      (node (ref "C12") (pin "1") (pinfunction "1_1") (pintype "passive"))
      (node (ref "U7") (pin "3") (pinfunction "-Vo_3") (pintype "passive"))
      (node (ref "U9") (pin "4") (pinfunction "GND1_4") (pintype "passive"))
    )
    (net (code "6") (name "/Gnd3") (class "Default")
      (node (ref "C4") (pin "1") (pinfunction "1_1") (pintype "passive"))
      (node (ref "C5") (pin "1") (pinfunction "1_1") (pintype "passive"))
      (node (ref "U3") (pin "3") (pinfunction "-Vo_3") (pintype "passive"))
      (node (ref "U5") (pin "4") (pinfunction "GND1_4") (pintype "passive"))
    )
    (net (code "7") (name "/I_U") (class "Default")
      (node (ref "P8") (pin "5") (pinfunction "5_5") (pintype "passive"))
      (node (ref "R30") (pin "2") (pinfunction "2_2") (pintype "passive"))
    )
    (net (code "8") (name "/I_V") (class "Default")
      (node (ref "P8") (pin "4") (pinfunction "4_4") (pintype "passive"))
      (node (ref "R25") (pin "2") (pinfunction "2_2") (pintype "passive"))
    )
    (net (code "9") (name "/I_W") (class "Default")
      (node (ref "P8") (pin "3") (pinfunction "3_3") (pintype "passive"))
      (node (ref "R18") (pin "2") (pinfunction "2_2") (pintype "passive"))
    )
    (net (code "10") (name "/PWM_FAN") (class "Default")
      (node (ref "P2") (pin "5") (pinfunction "5_5") (pintype "passive"))
      (node (ref "P7") (pin "4") (pinfunction "4_4") (pintype "passive"))
      (node (ref "XMC1") (pin "50") (pinfunction "P1.2_50") (pintype "input"))
    )
    (net (code "11") (name "/PWM_U") (class "Default")
      (node (ref "R11") (pin "2") (pinfunction "2_2") (pintype "passive"))
      (node (ref "U4") (pin "1") (pinfunction "1A_1") (pintype "passive"))
    )
    (net (code "12") (name "/PWM_V") (class "Default")
      (node (ref "R7") (pin "2") (pinfunction "2_2") (pintype "passive"))
      (node (ref "U2") (pin "1") (pinfunction "1A_1") (pintype "passive"))
    )
    (net (code "13") (name "/PWM_W") (class "Default")
      (node (ref "R8") (pin "1") (pinfunction "1_1") (pintype "passive"))
      (node (ref "U1") (pin "1") (pinfunction "1A_1") (pintype "passive"))
    )
    (net (code "14") (name "/Relay_1") (class "Default")
      (node (ref "P8") (pin "7") (pinfunction "7_7") (pintype "passive"))
      (node (ref "R15") (pin "2") (pinfunction "2_2") (pintype "passive"))
    )
    (net (code "15") (name "/Relay_2") (class "Default")
      (node (ref "P8") (pin "6") (pinfunction "6_6") (pintype "passive"))
      (node (ref "R16") (pin "2") (pinfunction "2_2") (pintype "passive"))
    )
    (net (code "16") (name "/TACH_FAN") (class "Default")
      (node (ref "P7") (pin "3") (pinfunction "3_3") (pintype "passive"))
      (node (ref "XMC1") (pin "18") (pinfunction "P0.10_18") (pintype "input"))
    )
    (net (code "17") (name "/V_DC") (class "Default")
      (node (ref "P7") (pin "7") (pinfunction "7_7") (pintype "passive"))
      (node (ref "R17") (pin "2") (pinfunction "2_2") (pintype "passive"))
    )
    (net (code "18") (name "/Vamp1") (class "Default")
      (node (ref "C14") (pin "1") (pinfunction "1_1") (pintype "passive"))
      (node (ref "R51") (pin "1") (pinfunction "1_1") (pintype "passive"))
      (node (ref "R57") (pin "2") (pinfunction "2_2") (pintype "passive"))
      (node (ref "U8") (pin "3") (pinfunction "In-_3") (pintype "passive"))
    )
    (net (code "19") (name "/Vamp2") (class "Default")
      (node (ref "C14") (pin "2") (pinfunction "2_2") (pintype "passive"))
      (node (ref "R51") (pin "2") (pinfunction "2_2") (pintype "passive"))
      (node (ref "R67") (pin "2") (pinfunction "2_2") (pintype "passive"))
      (node (ref "U8") (pin "2") (pinfunction "In+_2") (pintype "passive"))
    )
    (net (code "20") (name "/Vamp12") (class "Default")
      (node (ref "C16") (pin "1") (pinfunction "1_1") (pintype "passive"))
      (node (ref "R52") (pin "1") (pinfunction "1_1") (pintype "passive"))
      (node (ref "R62") (pin "2") (pinfunction "2_2") (pintype "passive"))
      (node (ref "U9") (pin "3") (pinfunction "In-_3") (pintype "passive"))
    )
    (net (code "21") (name "/Vamp13") (class "Default")
      (node (ref "C6") (pin "1") (pinfunction "1_1") (pintype "passive"))
      (node (ref "R36") (pin "1") (pinfunction "1_1") (pintype "passive"))
      (node (ref "R41") (pin "2") (pinfunction "2_2") (pintype "passive"))
      (node (ref "U5") (pin "3") (pinfunction "In-_3") (pintype "passive"))
    )
    (net (code "22") (name "/Vamp22") (class "Default")
      (node (ref "C16") (pin "2") (pinfunction "2_2") (pintype "passive"))
      (node (ref "R52") (pin "2") (pinfunction "2_2") (pintype "passive"))
      (node (ref "R72") (pin "2") (pinfunction "2_2") (pintype "passive"))
      (node (ref "U9") (pin "2") (pinfunction "In+_2") (pintype "passive"))
    )
    (net (code "23") (name "/Vamp23") (class "Default")
      (node (ref "C6") (pin "2") (pinfunction "2_2") (pintype "passive"))
      (node (ref "R36") (pin "2") (pinfunction "2_2") (pintype "passive"))
      (node (ref "R47") (pin "2") (pinfunction "2_2") (pintype "passive"))
      (node (ref "U5") (pin "2") (pinfunction "In+_2") (pintype "passive"))
    )
    (net (code "24") (name "/Vdd1") (class "Default")
      (node (ref "C10") (pin "2") (pinfunction "2_2") (pintype "passive"))
      (node (ref "C9") (pin "2") (pinfunction "2_2") (pintype "passive"))
      (node (ref "U6") (pin "4") (pinfunction "+Vo_4") (pintype "passive"))
      (node (ref "U8") (pin "1") (pinfunction "VDC1_1") (pintype "passive"))
    )
    (net (code "25") (name "/Vdd2") (class "Default")
      (node (ref "C11") (pin "2") (pinfunction "2_2") (pintype "passive"))
      (node (ref "C12") (pin "2") (pinfunction "2_2") (pintype "passive"))
      (node (ref "U7") (pin "4") (pinfunction "+Vo_4") (pintype "passive"))
      (node (ref "U9") (pin "1") (pinfunction "VDC1_1") (pintype "passive"))
    )
    (net (code "26") (name "/Vdd3") (class "Default")
      (node (ref "C4") (pin "2") (pinfunction "2_2") (pintype "passive"))
      (node (ref "C5") (pin "2") (pinfunction "2_2") (pintype "passive"))
      (node (ref "U3") (pin "4") (pinfunction "+Vo_4") (pintype "passive"))
      (node (ref "U5") (pin "1") (pinfunction "VDC1_1") (pintype "passive"))
    )
    (net (code "27") (name "/Vout1") (class "Default")
      (node (ref "C7") (pin "2") (pinfunction "2_2") (pintype "passive"))
      (node (ref "R19") (pin "2") (pinfunction "2_2") (pintype "passive"))
      (node (ref "R35") (pin "2") (pinfunction "2_2") (pintype "passive"))
    )
    (net (code "28") (name "/Vout2") (class "Default")
      (node (ref "C17") (pin "2") (pinfunction "2_2") (pintype "passive"))
      (node (ref "R26") (pin "2") (pinfunction "2_2") (pintype "passive"))
      (node (ref "R50") (pin "2") (pinfunction "2_2") (pintype "passive"))
    )
    (net (code "29") (name "/Vout3") (class "Default")
      (node (ref "C15") (pin "2") (pinfunction "2_2") (pintype "passive"))
      (node (ref "R31") (pin "2") (pinfunction "2_2") (pintype "passive"))
      (node (ref "R49") (pin "2") (pinfunction "2_2") (pintype "passive"))
    )
    (net (code "30") (name "/iabc_0") (class "Default")
      (node (ref "R30") (pin "1") (pinfunction "1_1") (pintype "passive"))
      (node (ref "R32") (pin "2") (pinfunction "2_2") (pintype "passive"))
      (node (ref "XMC1") (pin "36") (pinfunction "P14.8_36") (pintype "input"))
    )
    (net (code "31") (name "/iabc_1") (class "Default")
      (node (ref "P4") (pin "2") (pinfunction "2_2") (pintype "passive"))
      (node (ref "R25") (pin "1") (pinfunction "1_1") (pintype "passive"))
      (node (ref "R28") (pin "2") (pinfunction "2_2") (pintype "passive"))
      (node (ref "XMC1") (pin "33") (pinfunction "P14.2_33") (pintype "input"))
    )
    (net (code "32") (name "/iabc_2") (class "Default")
      (node (ref "R18") (pin "1") (pinfunction "1_1") (pintype "passive"))
      (node (ref "R22") (pin "2") (pinfunction "2_2") (pintype "passive"))
      (node (ref "XMC1") (pin "34") (pinfunction "P14.0_34") (pintype "input"))
    )
    (net (code "33") (name "/iso_ENA_UH") (class "Default")
      (node (ref "P1") (pin "7") (pinfunction "7_7") (pintype "passive"))
      (node (ref "R9") (pin "1") (pinfunction "1_1") (pintype "passive"))
    )
    (net (code "34") (name "/iso_ENA_UL") (class "Default")
      (node (ref "P6") (pin "7") (pinfunction "7_7") (pintype "passive"))
      (node (ref "R13") (pin "2") (pinfunction "2_2") (pintype "passive"))
    )
    (net (code "35") (name "/iso_ENA_VH") (class "Default")
      (node (ref "P1") (pin "6") (pinfunction "6_6") (pintype "passive"))
      (node (ref "R6") (pin "1") (pinfunction "1_1") (pintype "passive"))
    )
    (net (code "36") (name "/iso_ENA_VL") (class "Default")
      (node (ref "P6") (pin "6") (pinfunction "6_6") (pintype "passive"))
      (node (ref "R12") (pin "1") (pinfunction "1_1") (pintype "passive"))
    )
    (net (code "37") (name "/iso_ENA_WH") (class "Default")
      (node (ref "P1") (pin "5") (pinfunction "5_5") (pintype "passive"))
      (node (ref "R5") (pin "1") (pinfunction "1_1") (pintype "passive"))
    )
    (net (code "38") (name "/iso_ENA_WL") (class "Default")
      (node (ref "P6") (pin "5") (pinfunction "5_5") (pintype "passive"))
      (node (ref "R10") (pin "2") (pinfunction "2_2") (pintype "passive"))
    )
    (net (code "39") (name "/iso_PWM_UH") (class "Default")
      (node (ref "P1") (pin "4") (pinfunction "4_4") (pintype "passive"))
      (node (ref "R42") (pin "2") (pinfunction "2_2") (pintype "passive"))
    )
    (net (code "40") (name "/iso_PWM_UL") (class "Default")
      (node (ref "P6") (pin "4") (pinfunction "4_4") (pintype "passive"))
      (node (ref "R48") (pin "2") (pinfunction "2_2") (pintype "passive"))
    )
    (net (code "41") (name "/iso_PWM_VH") (class "Default")
      (node (ref "P1") (pin "3") (pinfunction "3_3") (pintype "passive"))
      (node (ref "R20") (pin "2") (pinfunction "2_2") (pintype "passive"))
    )
    (net (code "42") (name "/iso_PWM_VL") (class "Default")
      (node (ref "P6") (pin "3") (pinfunction "3_3") (pintype "passive"))
      (node (ref "R34") (pin "2") (pinfunction "2_2") (pintype "passive"))
    )
    (net (code "43") (name "/iso_PWM_WH") (class "Default")
      (node (ref "P1") (pin "2") (pinfunction "2_2") (pintype "passive"))
      (node (ref "R4") (pin "2") (pinfunction "2_2") (pintype "passive"))
    )
    (net (code "44") (name "/iso_PWM_WL") (class "Default")
      (node (ref "P6") (pin "2") (pinfunction "2_2") (pintype "passive"))
      (node (ref "R14") (pin "2") (pinfunction "2_2") (pintype "passive"))
    )
    (net (code "45") (name "/temp") (class "Default")
      (node (ref "P7") (pin "6") (pinfunction "6_6") (pintype "passive"))
      (node (ref "R24") (pin "2") (pinfunction "2_2") (pintype "passive"))
    )
    (net (code "46") (name "/temp_xmc") (class "Default")
      (node (ref "R24") (pin "1") (pinfunction "1_1") (pintype "passive"))
      (node (ref "R27") (pin "2") (pinfunction "2_2") (pintype "passive"))
      (node (ref "XMC1") (pin "12") (pinfunction "P14.13_12") (pintype "input"))
    )
    (net (code "47") (name "/v_dc_xmc") (class "Default")
      (node (ref "R17") (pin "1") (pinfunction "1_1") (pintype "passive"))
      (node (ref "R21") (pin "2") (pinfunction "2_2") (pintype "passive"))
      (node (ref "XMC1") (pin "11") (pinfunction "P14.7_11") (pintype "input"))
    )
    (net (code "48") (name "/vabc_0") (class "Default")
      (node (ref "R26") (pin "1") (pinfunction "1_1") (pintype "passive"))
      (node (ref "R29") (pin "2") (pinfunction "2_2") (pintype "passive"))
      (node (ref "XMC1") (pin "8") (pinfunction "P14.1_8") (pintype "input"))
    )
    (net (code "49") (name "/vabc_1") (class "Default")
      (node (ref "R19") (pin "1") (pinfunction "1_1") (pintype "passive"))
      (node (ref "R23") (pin "2") (pinfunction "2_2") (pintype "passive"))
      (node (ref "XMC1") (pin "9") (pinfunction "P14.3_9") (pintype "input"))
    )
    (net (code "50") (name "/vabc_2") (class "Default")
      (node (ref "R31") (pin "1") (pinfunction "1_1") (pintype "passive"))
      (node (ref "R33") (pin "2") (pinfunction "2_2") (pintype "passive"))
      (node (ref "XMC1") (pin "10") (pinfunction "P14.5_10") (pintype "input"))
    )
    (net (code "51") (name "3V3") (class "Default")
      (node (ref "C1") (pin "2") (pinfunction "2_2") (pintype "passive"))
      (node (ref "C2") (pin "2") (pinfunction "2_2") (pintype "passive"))
      (node (ref "C3") (pin "2") (pinfunction "2_2") (pintype "passive"))
      (node (ref "P7") (pin "1") (pinfunction "1_1") (pintype "passive"))
      (node (ref "P8") (pin "1") (pinfunction "1_1") (pintype "passive"))
      (node (ref "U1") (pin "14") (pinfunction "VCC_14") (pintype "passive"))
      (node (ref "U2") (pin "14") (pinfunction "VCC_14") (pintype "passive"))
      (node (ref "U4") (pin "14") (pinfunction "VCC_14") (pintype "passive"))
    )
    (net (code "52") (name "3V3GND") (class "Default")
      (node (ref "C1") (pin "1") (pinfunction "1_1") (pintype "passive"))
      (node (ref "C13") (pin "1") (pinfunction "1_1") (pintype "passive"))
      (node (ref "C15") (pin "1") (pinfunction "1_1") (pintype "passive"))
      (node (ref "C17") (pin "1") (pinfunction "1_1") (pintype "passive"))
      (node (ref "C18") (pin "1") (pinfunction "1_1") (pintype "passive"))
      (node (ref "C2") (pin "1") (pinfunction "1_1") (pintype "passive"))
      (node (ref "C3") (pin "1") (pinfunction "1_1") (pintype "passive"))
      (node (ref "C7") (pin "1") (pinfunction "1_1") (pintype "passive"))
      (node (ref "C8") (pin "1") (pinfunction "1_1") (pintype "passive"))
      (node (ref "P1") (pin "1") (pinfunction "1_1") (pintype "passive"))
      (node (ref "P1") (pin "8") (pinfunction "8_8") (pintype "passive"))
      (node (ref "P5") (pin "1") (pinfunction "1_1") (pintype "passive"))
      (node (ref "P5") (pin "2") (pinfunction "2_2") (pintype "passive"))
      (node (ref "P5") (pin "3") (pinfunction "3_3") (pintype "passive"))
      (node (ref "P5") (pin "4") (pinfunction "4_4") (pintype "passive"))
      (node (ref "P5") (pin "5") (pinfunction "5_5") (pintype "passive"))
      (node (ref "P5") (pin "6") (pinfunction "6_6") (pintype "passive"))
      (node (ref "P5") (pin "7") (pinfunction "7_7") (pintype "passive"))
      (node (ref "P5") (pin "8") (pinfunction "8_8") (pintype "passive"))
      (node (ref "P6") (pin "1") (pinfunction "1_1") (pintype "passive"))
      (node (ref "P6") (pin "8") (pinfunction "8_8") (pintype "passive"))
      (node (ref "P7") (pin "8") (pinfunction "8_8") (pintype "passive"))
      (node (ref "P8") (pin "8") (pinfunction "8_8") (pintype "passive"))
      (node (ref "R21") (pin "1") (pinfunction "1_1") (pintype "passive"))
      (node (ref "R22") (pin "1") (pinfunction "1_1") (pintype "passive"))
      (node (ref "R23") (pin "1") (pinfunction "1_1") (pintype "passive"))
      (node (ref "R27") (pin "1") (pinfunction "1_1") (pintype "passive"))
      (node (ref "R28") (pin "1") (pinfunction "1_1") (pintype "passive"))
      (node (ref "R29") (pin "1") (pinfunction "1_1") (pintype "passive"))
      (node (ref "R32") (pin "1") (pinfunction "1_1") (pintype "passive"))
      (node (ref "R33") (pin "1") (pinfunction "1_1") (pintype "passive"))
      (node (ref "U1") (pin "7") (pinfunction "GND_7") (pintype "passive"))
      (node (ref "U2") (pin "7") (pinfunction "GND_7") (pintype "passive"))
      (node (ref "U3") (pin "2") (pinfunction "GND_2") (pintype "passive"))
      (node (ref "U4") (pin "7") (pinfunction "GND_7") (pintype "passive"))
      (node (ref "U5") (pin "5") (pinfunction "GND2_5") (pintype "passive"))
      (node (ref "U5") (pin "6") (pinfunction "Out-_6") (pintype "passive"))
      (node (ref "U6") (pin "2") (pinfunction "GND_2") (pintype "passive"))
      (node (ref "U7") (pin "2") (pinfunction "GND_2") (pintype "passive"))
      (node (ref "U8") (pin "5") (pinfunction "GND2_5") (pintype "passive"))
      (node (ref "U8") (pin "6") (pinfunction "Out-_6") (pintype "passive"))
      (node (ref "U9") (pin "5") (pinfunction "GND2_5") (pintype "passive"))
      (node (ref "U9") (pin "6") (pinfunction "Out-_6") (pintype "passive"))
      (node (ref "XMC1") (pin "1") (pinfunction "GND_1") (pintype "power_in"))
      (node (ref "XMC1") (pin "2") (pinfunction "GND_2") (pintype "power_in"))
      (node (ref "XMC1") (pin "3") (pinfunction "GND_3") (pintype "power_in"))
      (node (ref "XMC1") (pin "39") (pinfunction "GND_39") (pintype "power_in"))
      (node (ref "XMC1") (pin "40") (pinfunction "GND_40") (pintype "power_in"))
      (node (ref "XMC1") (pin "41") (pinfunction "GND_41") (pintype "power_in"))
      (node (ref "XMC1") (pin "42") (pinfunction "GND_42") (pintype "power_in"))
      (node (ref "XMC1") (pin "58") (pinfunction "GND_58") (pintype "input"))
      (node (ref "XMC1") (pin "63") (pinfunction "GND_63") (pintype "input"))
      (node (ref "XMC1") (pin "79") (pinfunction "GND_79") (pintype "power_in"))
      (node (ref "XMC1") (pin "80") (pinfunction "GND_80") (pintype "power_in"))
    )
    (net (code "53") (name "5V") (class "Default")
      (node (ref "C13") (pin "2") (pinfunction "2_2") (pintype "passive"))
      (node (ref "C18") (pin "2") (pinfunction "2_2") (pintype "passive"))
      (node (ref "C8") (pin "2") (pinfunction "2_2") (pintype "passive"))
      (node (ref "P7") (pin "2") (pinfunction "2_2") (pintype "passive"))
      (node (ref "P8") (pin "2") (pinfunction "2_2") (pintype "passive"))
      (node (ref "U3") (pin "1") (pinfunction "Vin_1") (pintype "passive"))
      (node (ref "U5") (pin "8") (pinfunction "VDD2_8") (pintype "passive"))
      (node (ref "U6") (pin "1") (pinfunction "Vin_1") (pintype "passive"))
      (node (ref "U7") (pin "1") (pinfunction "Vin_1") (pintype "passive"))
      (node (ref "U8") (pin "8") (pinfunction "VDD2_8") (pintype "passive"))
      (node (ref "U9") (pin "8") (pinfunction "VDD2_8") (pintype "passive"))
      (node (ref "XMC1") (pin "20") (pinfunction "VDD5_20") (pintype "power_in"))
      (node (ref "XMC1") (pin "21") (pinfunction "VDD5_21") (pintype "power_in"))
      (node (ref "XMC1") (pin "60") (pinfunction "VDD5_60") (pintype "power_in"))
      (node (ref "XMC1") (pin "61") (pinfunction "VDD5_61") (pintype "power_in"))
    )
    (net (code "54") (name "Net-(P4-Pad1)") (class "Default")
      (node (ref "P4") (pin "1") (pinfunction "1_1") (pintype "passive"))
      (node (ref "P4") (pin "8") (pinfunction "8_8") (pintype "passive"))
      (node (ref "XMC1") (pin "22") (pinfunction "VDD3.3_22") (pintype "power_in"))
    )
    (net (code "55") (name "Net-(P9-Pad1)") (class "Default")
      (node (ref "P9") (pin "1") (pinfunction "1_1") (pintype "passive"))
      (node (ref "R43") (pin "1") (pinfunction "1_1") (pintype "passive"))
    )
    (net (code "56") (name "Net-(P9-Pad2)") (class "Default")
      (node (ref "P9") (pin "2") (pinfunction "2_2") (pintype "passive"))
      (node (ref "R37") (pin "1") (pinfunction "1_1") (pintype "passive"))
    )
    (net (code "57") (name "Net-(P10-Pad1)") (class "Default")
      (node (ref "P10") (pin "1") (pinfunction "1_1") (pintype "passive"))
      (node (ref "R63") (pin "1") (pinfunction "1_1") (pintype "passive"))
    )
    (net (code "58") (name "Net-(P10-Pad2)") (class "Default")
      (node (ref "P10") (pin "2") (pinfunction "2_2") (pintype "passive"))
      (node (ref "R53") (pin "1") (pinfunction "1_1") (pintype "passive"))
    )
    (net (code "59") (name "Net-(P11-Pad1)") (class "Default")
      (node (ref "P11") (pin "1") (pinfunction "1_1") (pintype "passive"))
      (node (ref "R68") (pin "1") (pinfunction "1_1") (pintype "passive"))
    )
    (net (code "60") (name "Net-(P11-Pad2)") (class "Default")
      (node (ref "P11") (pin "2") (pinfunction "2_2") (pintype "passive"))
      (node (ref "R58") (pin "1") (pinfunction "1_1") (pintype "passive"))
    )
    (net (code "61") (name "Net-(R37-Pad2)") (class "Default")
      (node (ref "R37") (pin "2") (pinfunction "2_2") (pintype "passive"))
      (node (ref "R38") (pin "1") (pinfunction "1_1") (pintype "passive"))
    )
    (net (code "62") (name "Net-(R38-Pad2)") (class "Default")
      (node (ref "R38") (pin "2") (pinfunction "2_2") (pintype "passive"))
      (node (ref "R39") (pin "1") (pinfunction "1_1") (pintype "passive"))
    )
    (net (code "63") (name "Net-(R39-Pad2)") (class "Default")
      (node (ref "R39") (pin "2") (pinfunction "2_2") (pintype "passive"))
      (node (ref "R40") (pin "1") (pinfunction "1_1") (pintype "passive"))
    )
    (net (code "64") (name "Net-(R40-Pad2)") (class "Default")
      (node (ref "R40") (pin "2") (pinfunction "2_2") (pintype "passive"))
      (node (ref "R41") (pin "1") (pinfunction "1_1") (pintype "passive"))
    )
    (net (code "65") (name "Net-(R43-Pad2)") (class "Default")
      (node (ref "R43") (pin "2") (pinfunction "2_2") (pintype "passive"))
      (node (ref "R44") (pin "1") (pinfunction "1_1") (pintype "passive"))
    )
    (net (code "66") (name "Net-(R44-Pad2)") (class "Default")
      (node (ref "R44") (pin "2") (pinfunction "2_2") (pintype "passive"))
      (node (ref "R45") (pin "1") (pinfunction "1_1") (pintype "passive"))
    )
    (net (code "67") (name "Net-(R45-Pad2)") (class "Default")
      (node (ref "R45") (pin "2") (pinfunction "2_2") (pintype "passive"))
      (node (ref "R46") (pin "1") (pinfunction "1_1") (pintype "passive"))
    )
    (net (code "68") (name "Net-(R46-Pad2)") (class "Default")
      (node (ref "R46") (pin "2") (pinfunction "2_2") (pintype "passive"))
      (node (ref "R47") (pin "1") (pinfunction "1_1") (pintype "passive"))
    )
    (net (code "69") (name "Net-(R53-Pad2)") (class "Default")
      (node (ref "R53") (pin "2") (pinfunction "2_2") (pintype "passive"))
      (node (ref "R54") (pin "1") (pinfunction "1_1") (pintype "passive"))
    )
    (net (code "70") (name "Net-(R54-Pad2)") (class "Default")
      (node (ref "R54") (pin "2") (pinfunction "2_2") (pintype "passive"))
      (node (ref "R55") (pin "1") (pinfunction "1_1") (pintype "passive"))
    )
    (net (code "71") (name "Net-(R55-Pad2)") (class "Default")
      (node (ref "R55") (pin "2") (pinfunction "2_2") (pintype "passive"))
      (node (ref "R56") (pin "1") (pinfunction "1_1") (pintype "passive"))
    )
    (net (code "72") (name "Net-(R56-Pad2)") (class "Default")
      (node (ref "R56") (pin "2") (pinfunction "2_2") (pintype "passive"))
      (node (ref "R57") (pin "1") (pinfunction "1_1") (pintype "passive"))
    )
    (net (code "73") (name "Net-(R58-Pad2)") (class "Default")
      (node (ref "R58") (pin "2") (pinfunction "2_2") (pintype "passive"))
      (node (ref "R59") (pin "1") (pinfunction "1_1") (pintype "passive"))
    )
    (net (code "74") (name "Net-(R59-Pad2)") (class "Default")
      (node (ref "R59") (pin "2") (pinfunction "2_2") (pintype "passive"))
      (node (ref "R60") (pin "1") (pinfunction "1_1") (pintype "passive"))
    )
    (net (code "75") (name "Net-(R60-Pad2)") (class "Default")
      (node (ref "R60") (pin "2") (pinfunction "2_2") (pintype "passive"))
      (node (ref "R61") (pin "1") (pinfunction "1_1") (pintype "passive"))
    )
    (net (code "76") (name "Net-(R61-Pad2)") (class "Default")
      (node (ref "R61") (pin "2") (pinfunction "2_2") (pintype "passive"))
      (node (ref "R62") (pin "1") (pinfunction "1_1") (pintype "passive"))
    )
    (net (code "77") (name "Net-(R63-Pad2)") (class "Default")
      (node (ref "R63") (pin "2") (pinfunction "2_2") (pintype "passive"))
      (node (ref "R64") (pin "1") (pinfunction "1_1") (pintype "passive"))
    )
    (net (code "78") (name "Net-(R64-Pad2)") (class "Default")
      (node (ref "R64") (pin "2") (pinfunction "2_2") (pintype "passive"))
      (node (ref "R65") (pin "1") (pinfunction "1_1") (pintype "passive"))
    )
    (net (code "79") (name "Net-(R65-Pad2)") (class "Default")
      (node (ref "R65") (pin "2") (pinfunction "2_2") (pintype "passive"))
      (node (ref "R66") (pin "1") (pinfunction "1_1") (pintype "passive"))
    )
    (net (code "80") (name "Net-(R66-Pad2)") (class "Default")
      (node (ref "R66") (pin "2") (pinfunction "2_2") (pintype "passive"))
      (node (ref "R67") (pin "1") (pinfunction "1_1") (pintype "passive"))
    )
    (net (code "81") (name "Net-(R68-Pad2)") (class "Default")
      (node (ref "R68") (pin "2") (pinfunction "2_2") (pintype "passive"))
      (node (ref "R69") (pin "1") (pinfunction "1_1") (pintype "passive"))
    )
    (net (code "82") (name "Net-(R69-Pad2)") (class "Default")
      (node (ref "R69") (pin "2") (pinfunction "2_2") (pintype "passive"))
      (node (ref "R70") (pin "1") (pinfunction "1_1") (pintype "passive"))
    )
    (net (code "83") (name "Net-(R70-Pad2)") (class "Default")
      (node (ref "R70") (pin "2") (pinfunction "2_2") (pintype "passive"))
      (node (ref "R71") (pin "1") (pinfunction "1_1") (pintype "passive"))
    )
    (net (code "84") (name "Net-(R71-Pad2)") (class "Default")
      (node (ref "R71") (pin "2") (pinfunction "2_2") (pintype "passive"))
      (node (ref "R72") (pin "1") (pinfunction "1_1") (pintype "passive"))
    )
    (net (code "85") (name "Net-(U1-1Y)") (class "Default")
      (node (ref "U1") (pin "3") (pinfunction "1Y_3") (pintype "passive"))
      (node (ref "U1") (pin "5") (pinfunction "2A_5") (pintype "passive"))
      (node (ref "U1") (pin "6") (pinfunction "2B_6") (pintype "passive"))
      (node (ref "U1") (pin "8") (pinfunction "3A_8") (pintype "passive"))
    )
    (net (code "86") (name "Net-(U1-2Y)") (class "Default")
      (node (ref "R4") (pin "1") (pinfunction "1_1") (pintype "passive"))
      (node (ref "U1") (pin "4") (pinfunction "2Y_4") (pintype "passive"))
    )
    (net (code "87") (name "Net-(U1-3Y)") (class "Default")
      (node (ref "U1") (pin "10") (pinfunction "3Y_10") (pintype "passive"))
      (node (ref "U1") (pin "12") (pinfunction "4A_12") (pintype "passive"))
      (node (ref "U1") (pin "13") (pinfunction "4B_13") (pintype "passive"))
    )
    (net (code "88") (name "Net-(U1-4Y)") (class "Default")
      (node (ref "R14") (pin "1") (pinfunction "1_1") (pintype "passive"))
      (node (ref "U1") (pin "11") (pinfunction "4Y_11") (pintype "passive"))
    )
    (net (code "89") (name "Net-(U2-1Y)") (class "Default")
      (node (ref "U2") (pin "3") (pinfunction "1Y_3") (pintype "passive"))
      (node (ref "U2") (pin "5") (pinfunction "2A_5") (pintype "passive"))
      (node (ref "U2") (pin "6") (pinfunction "2B_6") (pintype "passive"))
      (node (ref "U2") (pin "8") (pinfunction "3A_8") (pintype "passive"))
    )
    (net (code "90") (name "Net-(U2-2Y)") (class "Default")
      (node (ref "R20") (pin "1") (pinfunction "1_1") (pintype "passive"))
      (node (ref "U2") (pin "4") (pinfunction "2Y_4") (pintype "passive"))
    )
    (net (code "91") (name "Net-(U2-3Y)") (class "Default")
      (node (ref "U2") (pin "10") (pinfunction "3Y_10") (pintype "passive"))
      (node (ref "U2") (pin "12") (pinfunction "4A_12") (pintype "passive"))
      (node (ref "U2") (pin "13") (pinfunction "4B_13") (pintype "passive"))
    )
    (net (code "92") (name "Net-(U2-4Y)") (class "Default")
      (node (ref "R34") (pin "1") (pinfunction "1_1") (pintype "passive"))
      (node (ref "U2") (pin "11") (pinfunction "4Y_11") (pintype "passive"))
    )
    (net (code "93") (name "Net-(U4-1Y)") (class "Default")
      (node (ref "U4") (pin "3") (pinfunction "1Y_3") (pintype "passive"))
      (node (ref "U4") (pin "5") (pinfunction "2A_5") (pintype "passive"))
      (node (ref "U4") (pin "6") (pinfunction "2B_6") (pintype "passive"))
      (node (ref "U4") (pin "8") (pinfunction "3A_8") (pintype "passive"))
    )
    (net (code "94") (name "Net-(U4-2Y)") (class "Default")
      (node (ref "R42") (pin "1") (pinfunction "1_1") (pintype "passive"))
      (node (ref "U4") (pin "4") (pinfunction "2Y_4") (pintype "passive"))
    )
    (net (code "95") (name "Net-(U4-3Y)") (class "Default")
      (node (ref "U4") (pin "10") (pinfunction "3Y_10") (pintype "passive"))
      (node (ref "U4") (pin "12") (pinfunction "4A_12") (pintype "passive"))
      (node (ref "U4") (pin "13") (pinfunction "4B_13") (pintype "passive"))
    )
    (net (code "96") (name "Net-(U4-4Y)") (class "Default")
      (node (ref "R48") (pin "1") (pinfunction "1_1") (pintype "passive"))
      (node (ref "U4") (pin "11") (pinfunction "4Y_11") (pintype "passive"))
    )
    (net (code "97") (name "Net-(U5-Out+)") (class "Default")
      (node (ref "R35") (pin "1") (pinfunction "1_1") (pintype "passive"))
      (node (ref "U5") (pin "7") (pinfunction "Out+_7") (pintype "passive"))
    )
    (net (code "98") (name "Net-(U8-Out+)") (class "Default")
      (node (ref "R49") (pin "1") (pinfunction "1_1") (pintype "passive"))
      (node (ref "U8") (pin "7") (pinfunction "Out+_7") (pintype "passive"))
    )
    (net (code "99") (name "Net-(U9-Out+)") (class "Default")
      (node (ref "R50") (pin "1") (pinfunction "1_1") (pintype "passive"))
      (node (ref "U9") (pin "7") (pinfunction "Out+_7") (pintype "passive"))
    )
    (net (code "100") (name "Net-(XMC1A-P0.2)") (class "Default")
      (node (ref "R9") (pin "2") (pinfunction "2_2") (pintype "passive"))
      (node (ref "XMC1") (pin "65") (pinfunction "P0.2_65") (pintype "input"))
    )
    (net (code "101") (name "Net-(XMC1A-P0.4)") (class "Default")
      (node (ref "R11") (pin "1") (pinfunction "1_1") (pintype "passive"))
      (node (ref "XMC1") (pin "64") (pinfunction "P0.4_64") (pintype "input"))
    )
    (net (code "102") (name "Net-(XMC1A-P0.5)") (class "Default")
      (node (ref "R8") (pin "2") (pinfunction "2_2") (pintype "passive"))
      (node (ref "XMC1") (pin "56") (pinfunction "P0.5_56") (pintype "input"))
    )
    (net (code "103") (name "Net-(XMC1A-P0.6)") (class "Default")
      (node (ref "R7") (pin "1") (pinfunction "1_1") (pintype "passive"))
      (node (ref "XMC1") (pin "66") (pinfunction "P0.6_66") (pintype "input"))
    )
    (net (code "104") (name "Net-(XMC1A-P0.7)") (class "Default")
      (node (ref "P2") (pin "8") (pinfunction "8_8") (pintype "passive"))
      (node (ref "XMC1") (pin "53") (pinfunction "P0.7_53") (pintype "input"))
    )
    (net (code "105") (name "Net-(XMC1A-P0.8)") (class "Default")
      (node (ref "P3") (pin "7") (pinfunction "7_7") (pintype "passive"))
      (node (ref "XMC1") (pin "69") (pinfunction "P0.8_69") (pintype "input"))
    )
    (net (code "106") (name "Net-(XMC1A-P0.11)") (class "Default")
      (node (ref "R6") (pin "2") (pinfunction "2_2") (pintype "passive"))
      (node (ref "XMC1") (pin "55") (pinfunction "P0.11_55") (pintype "input"))
    )
    (net (code "107") (name "Net-(XMC1A-P1.0)") (class "Default")
      (node (ref "P2") (pin "6") (pinfunction "6_6") (pintype "passive"))
      (node (ref "XMC1") (pin "51") (pinfunction "P1.0_51") (pintype "input"))
    )
    (net (code "108") (name "Net-(XMC1A-P1.1)") (class "Default")
      (node (ref "P3") (pin "5") (pinfunction "5_5") (pintype "passive"))
      (node (ref "XMC1") (pin "71") (pinfunction "P1.1_71") (pintype "input"))
    )
    (net (code "109") (name "Net-(XMC1A-P1.3)") (class "Default")
      (node (ref "P3") (pin "4") (pinfunction "4_4") (pintype "passive"))
      (node (ref "XMC1") (pin "72") (pinfunction "P1.3_72") (pintype "input"))
    )
    (net (code "110") (name "Net-(XMC1A-P1.4)") (class "Default")
      (node (ref "P2") (pin "4") (pinfunction "4_4") (pintype "passive"))
      (node (ref "XMC1") (pin "49") (pinfunction "P1.4_49") (pintype "input"))
    )
    (net (code "111") (name "Net-(XMC1A-P1.5)") (class "Default")
      (node (ref "P3") (pin "3") (pinfunction "3_3") (pintype "passive"))
      (node (ref "XMC1") (pin "73") (pinfunction "P1.5_73") (pintype "input"))
    )
    (net (code "112") (name "Net-(XMC1A-P1.8)") (class "Default")
      (node (ref "P2") (pin "7") (pinfunction "7_7") (pintype "passive"))
      (node (ref "XMC1") (pin "52") (pinfunction "P1.8_52") (pintype "input"))
    )
    (net (code "113") (name "Net-(XMC1A-P1.9)") (class "Default")
      (node (ref "P3") (pin "6") (pinfunction "6_6") (pintype "passive"))
      (node (ref "XMC1") (pin "70") (pinfunction "P1.9_70") (pintype "input"))
    )
    (net (code "114") (name "Net-(XMC1A-P1.10)") (class "Default")
      (node (ref "P2") (pin "3") (pinfunction "3_3") (pintype "passive"))
      (node (ref "XMC1") (pin "48") (pinfunction "P1.10_48") (pintype "input"))
    )
    (net (code "115") (name "Net-(XMC1A-P1.11)") (class "Default")
      (node (ref "P3") (pin "2") (pinfunction "2_2") (pintype "passive"))
      (node (ref "XMC1") (pin "74") (pinfunction "P1.11_74") (pintype "input"))
    )
    (net (code "116") (name "Net-(XMC1A-P1.12)") (class "Default")
      (node (ref "P2") (pin "2") (pinfunction "2_2") (pintype "passive"))
      (node (ref "XMC1") (pin "47") (pinfunction "P1.12_47") (pintype "input"))
    )
    (net (code "117") (name "Net-(XMC1A-P1.13)") (class "Default")
      (node (ref "P3") (pin "1") (pinfunction "1_1") (pintype "passive"))
      (node (ref "XMC1") (pin "75") (pinfunction "P1.13_75") (pintype "input"))
    )
    (net (code "118") (name "Net-(XMC1A-P1.14)") (class "Default")
      (node (ref "P2") (pin "1") (pinfunction "1_1") (pintype "passive"))
      (node (ref "XMC1") (pin "46") (pinfunction "P1.14_46") (pintype "input"))
    )
    (net (code "119") (name "Net-(XMC1A-P2.6)") (class "Default")
      (node (ref "R1") (pin "2") (pinfunction "2_2") (pintype "passive"))
      (node (ref "XMC1") (pin "43") (pinfunction "P2.6_43") (pintype "power_in"))
    )
    (net (code "120") (name "Net-(XMC1A-P3.3)") (class "Default")
      (node (ref "R5") (pin "2") (pinfunction "2_2") (pintype "passive"))
      (node (ref "XMC1") (pin "54") (pinfunction "P3.3_54") (pintype "input"))
    )
    (net (code "121") (name "Net-(XMC1A-P3.4)") (class "Default")
      (node (ref "P3") (pin "8") (pinfunction "8_8") (pintype "passive"))
      (node (ref "XMC1") (pin "68") (pinfunction "P3.4_68") (pintype "input"))
    )
    (net (code "122") (name "Net-(XMC1A-P5.0)") (class "Default")
      (node (ref "R3") (pin "2") (pinfunction "2_2") (pintype "passive"))
      (node (ref "XMC1") (pin "45") (pinfunction "P5.0_45") (pintype "input"))
    )
    (net (code "123") (name "Net-(XMC1A-P5.2)") (class "Default")
      (node (ref "R2") (pin "2") (pinfunction "2_2") (pintype "passive"))
      (node (ref "XMC1") (pin "44") (pinfunction "P5.2_44") (pintype "input"))
    )
    (net (code "124") (name "Net-(XMC1B-P0.0)") (class "Default")
      (node (ref "R16") (pin "1") (pinfunction "1_1") (pintype "passive"))
      (node (ref "XMC1") (pin "23") (pinfunction "P0.0_23") (pintype "input"))
    )
    (net (code "125") (name "Net-(XMC1B-P0.1)") (class "Default")
      (node (ref "R15") (pin "1") (pinfunction "1_1") (pintype "passive"))
      (node (ref "XMC1") (pin "24") (pinfunction "P0.1_24") (pintype "input"))
    )
    (net (code "126") (name "Net-(XMC1B-P3.0)") (class "Default")
      (node (ref "R10") (pin "1") (pinfunction "1_1") (pintype "passive"))
      (node (ref "XMC1") (pin "26") (pinfunction "P3.0_26") (pintype "input"))
    )
    (net (code "127") (name "Net-(XMC1B-P3.1)") (class "Default")
      (node (ref "R12") (pin "2") (pinfunction "2_2") (pintype "passive"))
      (node (ref "XMC1") (pin "16") (pinfunction "P3.1_16") (pintype "input"))
    )
    (net (code "128") (name "Net-(XMC1B-P3.2)") (class "Default")
      (node (ref "R13") (pin "1") (pinfunction "1_1") (pintype "passive"))
      (node (ref "XMC1") (pin "25") (pinfunction "P3.2_25") (pintype "input"))
    )
    (net (code "129") (name "Net-(XMC1B-P14.4)") (class "Default")
      (node (ref "P4") (pin "3") (pinfunction "3_3") (pintype "passive"))
      (node (ref "XMC1") (pin "32") (pinfunction "P14.4_32") (pintype "input"))
    )
    (net (code "130") (name "Net-(XMC1B-P14.6)") (class "Default")
      (node (ref "P4") (pin "4") (pinfunction "4_4") (pintype "passive"))
      (node (ref "XMC1") (pin "31") (pinfunction "P14.6_31") (pintype "input"))
    )
    (net (code "131") (name "Net-(XMC1B-P14.12)") (class "Default")
      (node (ref "P4") (pin "5") (pinfunction "5_5") (pintype "passive"))
      (node (ref "XMC1") (pin "30") (pinfunction "P14.12_30") (pintype "input"))
    )
    (net (code "132") (name "Net-(XMC1B-P14.14)") (class "Default")
      (node (ref "P4") (pin "6") (pinfunction "6_6") (pintype "passive"))
      (node (ref "XMC1") (pin "29") (pinfunction "P14.14_29") (pintype "input"))
    )
    (net (code "133") (name "Net-(XMC1B-P15.2)") (class "Default")
      (node (ref "P4") (pin "7") (pinfunction "7_7") (pintype "passive"))
      (node (ref "XMC1") (pin "28") (pinfunction "P15.2_28") (pintype "input"))
    )
    (net (code "134") (name "unconnected-(P7-Pad5)") (class "Default")
      (node (ref "P7") (pin "5") (pinfunction "5_5") (pintype "passive+no_connect"))
    )
    (net (code "135") (name "unconnected-(XMC1A-P0.3-Pad57)") (class "Default")
      (node (ref "XMC1") (pin "57") (pinfunction "P0.3_57") (pintype "input"))
    )
    (net (code "136") (name "unconnected-(XMC1A-P0.12-Pad67)") (class "Default")
      (node (ref "XMC1") (pin "67") (pinfunction "P0.12_67") (pintype "input"))
    )
    (net (code "137") (name "unconnected-(XMC1A-P1.15-Pad76)") (class "Default")
      (node (ref "XMC1") (pin "76") (pinfunction "P1.15_76") (pintype "input"))
    )
    (net (code "138") (name "unconnected-(XMC1A-P5.1-Pad77)") (class "Default")
      (node (ref "XMC1") (pin "77") (pinfunction "P5.1_77") (pintype "input"))
    )
    (net (code "139") (name "unconnected-(XMC1A-P5.7-Pad78)") (class "Default")
      (node (ref "XMC1") (pin "78") (pinfunction "P5.7_78") (pintype "input"))
    )
    (net (code "140") (name "unconnected-(XMC1A-VDD3.3-Pad59)") (class "Default")
      (node (ref "XMC1") (pin "59") (pinfunction "VDD3.3_59") (pintype "power_in"))
    )
    (net (code "141") (name "unconnected-(XMC1A-VDD3.3-Pad62)") (class "Default")
      (node (ref "XMC1") (pin "62") (pinfunction "VDD3.3_62") (pintype "power_in"))
    )
    (net (code "142") (name "unconnected-(XMC1B-HIB_0-Pad27)") (class "Default")
      (node (ref "XMC1") (pin "27") (pinfunction "HIB_0_27") (pintype "input"))
    )
    (net (code "143") (name "unconnected-(XMC1B-HIB_1-Pad15)") (class "Default")
      (node (ref "XMC1") (pin "15") (pinfunction "HIB_1_15") (pintype "input"))
    )
    (net (code "144") (name "unconnected-(XMC1B-P0.9-Pad17)") (class "Default")
      (node (ref "XMC1") (pin "17") (pinfunction "P0.9_17") (pintype "input"))
    )
    (net (code "145") (name "unconnected-(XMC1B-P2.1-Pad4)") (class "Default")
      (node (ref "XMC1") (pin "4") (pinfunction "P2.1_4") (pintype "input"))
    )
    (net (code "146") (name "unconnected-(XMC1B-P2.10-Pad37)") (class "Default")
      (node (ref "XMC1") (pin "37") (pinfunction "P2.10_37") (pintype "input"))
    )
    (net (code "147") (name "unconnected-(XMC1B-P2.14-Pad5)") (class "Default")
      (node (ref "XMC1") (pin "5") (pinfunction "P2.14_5") (pintype "input"))
    )
    (net (code "148") (name "unconnected-(XMC1B-P2.15-Pad6)") (class "Default")
      (node (ref "XMC1") (pin "6") (pinfunction "P2.15_6") (pintype "input"))
    )
    (net (code "149") (name "unconnected-(XMC1B-P14.9-Pad35)") (class "Default")
      (node (ref "XMC1") (pin "35") (pinfunction "P14.9_35") (pintype "input"))
    )
    (net (code "150") (name "unconnected-(XMC1B-P14.15-Pad13)") (class "Default")
      (node (ref "XMC1") (pin "13") (pinfunction "P14.15_13") (pintype "input"))
    )
    (net (code "151") (name "unconnected-(XMC1B-P15.3-Pad14)") (class "Default")
      (node (ref "XMC1") (pin "14") (pinfunction "P15.3_14") (pintype "input"))
    )
    (net (code "152") (name "unconnected-(XMC1B-RST-Pad38)") (class "Default")
      (node (ref "XMC1") (pin "38") (pinfunction "RST_38") (pintype "input"))
    )
    (net (code "153") (name "unconnected-(XMC1B-VAREF-Pad7)") (class "Default")
      (node (ref "XMC1") (pin "7") (pinfunction "VAREF_7") (pintype "input"))
    )
    (net (code "154") (name "unconnected-(XMC1B-VDD3.3-Pad19)") (class "Default")
      (node (ref "XMC1") (pin "19") (pinfunction "VDD3.3_19") (pintype "power_in"))
    )
  )
)
